# RFID_DC_Sch.net
KiCad netlist of a schematic drawn in Altium Designer
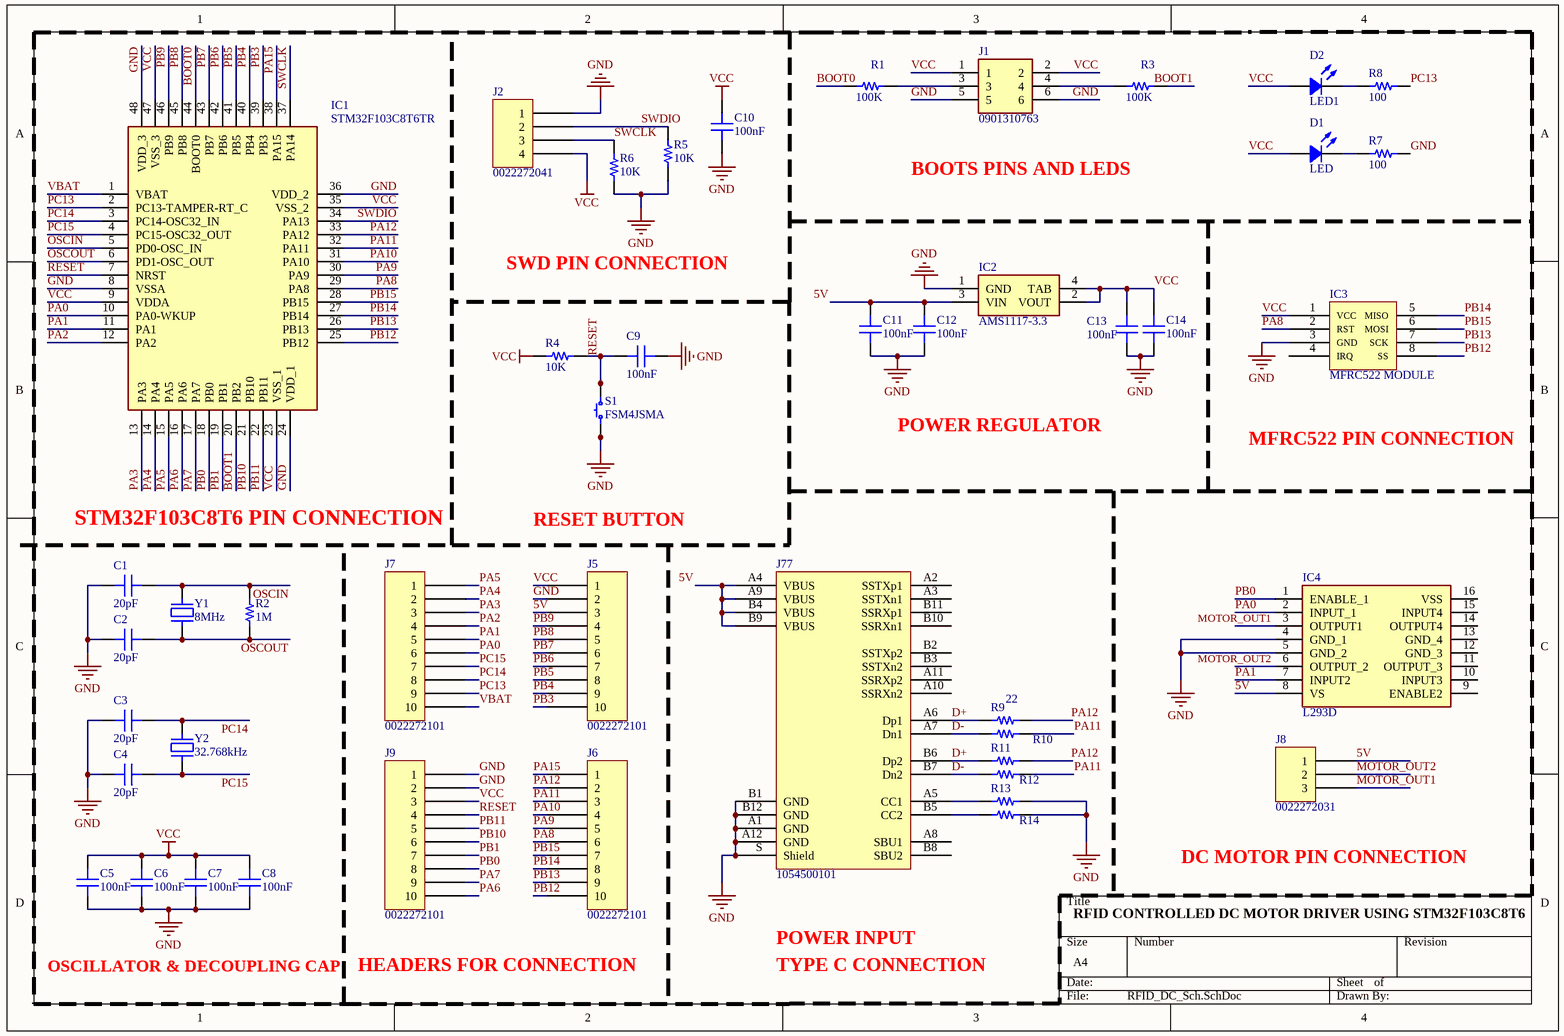
[diagram p0: RFID_DC_Sch.SchDoc]

(export (version "E")
  (design (tool "Eeschema 10.0.6"))
  (components
    (comp (ref "C1")
      (value "20pF")
      (footprint "CAP 0805_2012")
      (description "CAP CER 0.1UF 16V Y5V 0805")
      (fields (field (name "PART NUMBER") "C0805C104M4VACTU") (field (name "MANUFACTURER") "KEMET"))
      (libsource (lib "Celestial Altium Library - altium_library") (part "Capacitor"))
    )
    (comp (ref "C2")
      (value "20pF")
      (footprint "CAP 0805_2012")
      (description "CAP CER 0.1UF 16V Y5V 0805")
      (fields (field (name "PART NUMBER") "C0805C104M4VACTU") (field (name "MANUFACTURER") "KEMET"))
      (libsource (lib "Celestial Altium Library - altium_library") (part "Capacitor"))
    )
    (comp (ref "C3")
      (value "20pF")
      (footprint "CAP 0805_2012")
      (description "CAP CER 0.1UF 16V Y5V 0805")
      (fields (field (name "PART NUMBER") "C0805C104M4VACTU") (field (name "MANUFACTURER") "KEMET"))
      (libsource (lib "Celestial Altium Library - altium_library") (part "Capacitor"))
    )
    (comp (ref "C4")
      (value "20pF")
      (footprint "CAP 0805_2012")
      (description "CAP CER 0.1UF 16V Y5V 0805")
      (fields (field (name "PART NUMBER") "C0805C104M4VACTU") (field (name "MANUFACTURER") "KEMET"))
      (libsource (lib "Celestial Altium Library - altium_library") (part "Capacitor"))
    )
    (comp (ref "C5")
      (value "100nF")
      (footprint "CAP 0805_2012")
      (description "CAP CER 0.1UF 16V Y5V 0805")
      (fields (field (name "PART NUMBER") "C0805C104M4VACTU") (field (name "MANUFACTURER") "KEMET"))
      (libsource (lib "Celestial Altium Library - altium_library") (part "Capacitor"))
    )
    (comp (ref "C6")
      (value "100nF")
      (footprint "CAP 0805_2012")
      (description "CAP CER 0.1UF 16V Y5V 0805")
      (fields (field (name "PART NUMBER") "C0805C104M4VACTU") (field (name "MANUFACTURER") "KEMET"))
      (libsource (lib "Celestial Altium Library - altium_library") (part "Capacitor"))
    )
    (comp (ref "C7")
      (value "100nF")
      (footprint "CAP 0805_2012")
      (description "CAP CER 0.1UF 16V Y5V 0805")
      (fields (field (name "PART NUMBER") "C0805C104M4VACTU") (field (name "MANUFACTURER") "KEMET"))
      (libsource (lib "Celestial Altium Library - altium_library") (part "Capacitor"))
    )
    (comp (ref "C8")
      (value "100nF")
      (footprint "CAP 0805_2012")
      (description "CAP CER 0.1UF 16V Y5V 0805")
      (fields (field (name "PART NUMBER") "C0805C104M4VACTU") (field (name "MANUFACTURER") "KEMET"))
      (libsource (lib "Celestial Altium Library - altium_library") (part "Capacitor"))
    )
    (comp (ref "C9")
      (value "100nF")
      (footprint "CAP 0805_2012")
      (description "CAP CER 0.1UF 16V Y5V 0805")
      (fields (field (name "PART NUMBER") "C0805C104M4VACTU") (field (name "MANUFACTURER") "KEMET"))
      (libsource (lib "Celestial Altium Library - altium_library") (part "Capacitor"))
    )
    (comp (ref "C10")
      (value "100nF")
      (footprint "CAP 0805_2012")
      (description "CAP CER 0.1UF 16V Y5V 0805")
      (fields (field (name "PART NUMBER") "C0805C104M4VACTU") (field (name "MANUFACTURER") "KEMET"))
      (libsource (lib "Celestial Altium Library - altium_library") (part "Capacitor"))
    )
    (comp (ref "C11")
      (value "100nF")
      (footprint "CAP 0805_2012")
      (description "CAP CER 0.1UF 16V Y5V 0805")
      (fields (field (name "PART NUMBER") "C0805C104M4VACTU") (field (name "MANUFACTURER") "KEMET"))
      (libsource (lib "Celestial Altium Library - altium_library") (part "Capacitor"))
    )
    (comp (ref "C12")
      (value "100nF")
      (footprint "CAP 0805_2012")
      (description "CAP CER 0.1UF 16V Y5V 0805")
      (fields (field (name "PART NUMBER") "C0805C104M4VACTU") (field (name "MANUFACTURER") "KEMET"))
      (libsource (lib "Celestial Altium Library - altium_library") (part "Capacitor"))
    )
    (comp (ref "C13")
      (value "100nF")
      (footprint "CAP 0805_2012")
      (description "CAP CER 0.1UF 16V Y5V 0805")
      (fields (field (name "PART NUMBER") "C0805C104M4VACTU") (field (name "MANUFACTURER") "KEMET"))
      (libsource (lib "Celestial Altium Library - altium_library") (part "Capacitor"))
    )
    (comp (ref "C14")
      (value "100nF")
      (footprint "CAP 0805_2012")
      (description "CAP CER 0.1UF 16V Y5V 0805")
      (fields (field (name "PART NUMBER") "C0805C104M4VACTU") (field (name "MANUFACTURER") "KEMET"))
      (libsource (lib "Celestial Altium Library - altium_library") (part "Capacitor"))
    )
    (comp (ref "D1")
      (value "LED")
      (footprint "CREE J 2835")
      (description "LED WHITE  4000K JE2835 3V")
      (fields
        (field (name "PART NUMBER") "JE2835AWT-R-U40GA0000-N0000001")
        (field (name "MANUFACTURER") "Cree Inc.")
      )
      (libsource (lib "Celestial Altium Library - altium_library") (part "LED"))
    )
    (comp (ref "D2")
      (value "LED1")
      (footprint "CREE J 2835")
      (description "LED WHITE  4000K JE2835 3V")
      (fields
        (field (name "PART NUMBER") "JE2835AWT-R-U40GA0000-N0000001")
        (field (name "MANUFACTURER") "Cree Inc.")
      )
      (libsource (lib "Celestial Altium Library - altium_library") (part "LED"))
    )
    (comp (ref "IC1")
      (value "STM32F103C8T6TR")
      (footprint "SamacSys:QFP50P900X900X160-48N")
      (description "Integrated Circuit")
      (fields (field (name "MOUSER PART NUMBER") "511-STM32F103C8T6TR"))
      (libsource (lib "SamacSys") (part "STM32F103C8T6TR"))
    )
    (comp (ref "IC2")
      (value "AMS1117-3.3")
      (footprint "SamacSys:SOT229P700X180-4N")
      (description "Integrated Circuit")
      (libsource (lib "SamacSys") (part "AMS1117-3.3"))
    )
    (comp (ref "IC3")
      (value "MFRC522 MODULE")
      (footprint "RC522")
      (description "RFID MODULE")
      (libsource (lib "SamacSys") (part "MFRC522 MODULE"))
    )
    (comp (ref "IC4")
      (value "L293D")
      (footprint "DIP880W50P254L2000H510Q16N")
      (description "Integrated Circuit")
      (fields (field (name "MOUSER PART NUMBER") "511-L293D"))
      (libsource (lib "SamacSys") (part "L293D"))
    )
    (comp (ref "J1")
      (value "0901310763")
      (footprint "SamacSys:HDRV6W90P254_2X3_762X500X560P")
      (description "Connector")
      (libsource (lib "SamacSys") (part "0901310763"))
    )
    (comp (ref "J2")
      (value "0022272041")
      (footprint "MOLEX KK 0022272041")
      (description "CONN HEADER VERT 4POS 2.54MM")
      (fields (field (name "MANUFACTURER") "Molex"))
      (libsource (lib "Celestial Altium Library - altium_library") (part "4 Pin"))
    )
    (comp (ref "J5")
      (value "0022272101")
      (footprint "MOLEX KK 0022272101")
      (description "CONN HEADER VERT 10POS 2.54MM")
      (fields (field (name "MANUFACTURER") "Molex"))
      (libsource (lib "Celestial Altium Library - altium_library") (part "10 Pin"))
    )
    (comp (ref "J6")
      (value "0022272101")
      (footprint "MOLEX KK 0022272101")
      (description "CONN HEADER VERT 10POS 2.54MM")
      (fields (field (name "MANUFACTURER") "Molex"))
      (libsource (lib "Celestial Altium Library - altium_library") (part "10 Pin"))
    )
    (comp (ref "J7")
      (value "0022272101")
      (footprint "MOLEX KK 0022272101")
      (description "CONN HEADER VERT 10POS 2.54MM")
      (fields (field (name "MANUFACTURER") "Molex"))
      (libsource (lib "") (part "10 Pin_1"))
    )
    (comp (ref "J8")
      (value "0022272031")
      (footprint "MOLEX KK 0022272031")
      (description "CONN HEADER VERT 3POS 2.54MM")
      (fields (field (name "MANUFACTURER") "Molex"))
      (libsource (lib "Celestial Altium Library - altium_library") (part "3 Pin"))
    )
    (comp (ref "J9")
      (value "0022272101")
      (footprint "MOLEX KK 0022272101")
      (description "CONN HEADER VERT 10POS 2.54MM")
      (fields (field (name "MANUFACTURER") "Molex"))
      (libsource (lib "") (part "10 Pin_1"))
    )
    (comp (ref "J77")
      (value "1054500101")
      (footprint "Molex 1054500101")
      (description "CONN RCP USB3.1 TYPEC 24P SMD RA")
      (fields (field (name "MANUFACTURER") "Molex"))
      (libsource (lib "Celestial Altium Library - altium_library") (part "USB 3.0 Type C"))
    )
    (comp (ref "R1")
      (value "100K")
      (footprint "RES 0805_2012")
      (description "RES 931K OHM 1% 1/8W 0805")
      (fields
        (field (name "PART NUMBER") "RMCF0805FT931K")
        (field (name "MANUFACTURER") "Stackpole Electronics Inc")
      )
      (libsource (lib "Celestial Altium Library - altium_library") (part "Resistor"))
    )
    (comp (ref "R2")
      (value "1M")
      (footprint "RES 0805_2012")
      (description "RES 931K OHM 1% 1/8W 0805")
      (fields
        (field (name "PART NUMBER") "RMCF0805FT931K")
        (field (name "MANUFACTURER") "Stackpole Electronics Inc")
      )
      (libsource (lib "Celestial Altium Library - altium_library") (part "Resistor"))
    )
    (comp (ref "R3")
      (value "100K")
      (footprint "RES 0805_2012")
      (description "RES 931K OHM 1% 1/8W 0805")
      (fields
        (field (name "PART NUMBER") "RMCF0805FT931K")
        (field (name "MANUFACTURER") "Stackpole Electronics Inc")
      )
      (libsource (lib "Celestial Altium Library - altium_library") (part "Resistor"))
    )
    (comp (ref "R4")
      (value "10K")
      (footprint "RES 0805_2012")
      (description "RES 931K OHM 1% 1/8W 0805")
      (fields
        (field (name "PART NUMBER") "RMCF0805FT931K")
        (field (name "MANUFACTURER") "Stackpole Electronics Inc")
      )
      (libsource (lib "Celestial Altium Library - altium_library") (part "Resistor"))
    )
    (comp (ref "R5")
      (value "10K")
      (footprint "RES 0805_2012")
      (description "RES 931K OHM 1% 1/8W 0805")
      (fields
        (field (name "PART NUMBER") "RMCF0805FT931K")
        (field (name "MANUFACTURER") "Stackpole Electronics Inc")
      )
      (libsource (lib "Celestial Altium Library - altium_library") (part "Resistor"))
    )
    (comp (ref "R6")
      (value "10K")
      (footprint "RES 0805_2012")
      (description "RES 931K OHM 1% 1/8W 0805")
      (fields
        (field (name "PART NUMBER") "RMCF0805FT931K")
        (field (name "MANUFACTURER") "Stackpole Electronics Inc")
      )
      (libsource (lib "Celestial Altium Library - altium_library") (part "Resistor"))
    )
    (comp (ref "R7")
      (value "100")
      (footprint "RES 0805_2012")
      (description "RES 931K OHM 1% 1/8W 0805")
      (fields
        (field (name "PART NUMBER") "RMCF0805FT931K")
        (field (name "MANUFACTURER") "Stackpole Electronics Inc")
      )
      (libsource (lib "Celestial Altium Library - altium_library") (part "Resistor"))
    )
    (comp (ref "R8")
      (value "100")
      (footprint "RES 0805_2012")
      (description "RES 931K OHM 1% 1/8W 0805")
      (fields
        (field (name "PART NUMBER") "RMCF0805FT931K")
        (field (name "MANUFACTURER") "Stackpole Electronics Inc")
      )
      (libsource (lib "Celestial Altium Library - altium_library") (part "Resistor"))
    )
    (comp (ref "R9")
      (value "22")
      (footprint "RES 0805_2012")
      (description "RES 931K OHM 1% 1/8W 0805")
      (fields
        (field (name "PART NUMBER") "RMCF0805FT931K")
        (field (name "MANUFACTURER") "Stackpole Electronics Inc")
      )
      (libsource (lib "Celestial Altium Library - altium_library") (part "Resistor"))
    )
    (comp (ref "R10")
      (value "~")
      (footprint "RES 0805_2012")
      (description "RES 931K OHM 1% 1/8W 0805")
      (fields
        (field (name "PART NUMBER") "RMCF0805FT931K")
        (field (name "MANUFACTURER") "Stackpole Electronics Inc")
      )
      (libsource (lib "Celestial Altium Library - altium_library") (part "Resistor"))
    )
    (comp (ref "R11")
      (value "~")
      (footprint "RES 0805_2012")
      (description "RES 931K OHM 1% 1/8W 0805")
      (fields
        (field (name "PART NUMBER") "RMCF0805FT931K")
        (field (name "MANUFACTURER") "Stackpole Electronics Inc")
      )
      (libsource (lib "Celestial Altium Library - altium_library") (part "Resistor"))
    )
    (comp (ref "R12")
      (value "~")
      (footprint "RES 0805_2012")
      (description "RES 931K OHM 1% 1/8W 0805")
      (fields
        (field (name "PART NUMBER") "RMCF0805FT931K")
        (field (name "MANUFACTURER") "Stackpole Electronics Inc")
      )
      (libsource (lib "Celestial Altium Library - altium_library") (part "Resistor"))
    )
    (comp (ref "R13")
      (value "~")
      (footprint "RES 0805_2012")
      (description "RES 931K OHM 1% 1/8W 0805")
      (fields
        (field (name "PART NUMBER") "RMCF0805FT931K")
        (field (name "MANUFACTURER") "Stackpole Electronics Inc")
      )
      (libsource (lib "Celestial Altium Library - altium_library") (part "Resistor"))
    )
    (comp (ref "R14")
      (value "~")
      (footprint "RES 0805_2012")
      (description "RES 931K OHM 1% 1/8W 0805")
      (fields
        (field (name "PART NUMBER") "RMCF0805FT931K")
        (field (name "MANUFACTURER") "Stackpole Electronics Inc")
      )
      (libsource (lib "Celestial Altium Library - altium_library") (part "Resistor"))
    )
    (comp (ref "S1")
      (value "FSM4JSMA")
      (footprint "TE FSM4JSMA")
      (description "SWITCH TACTILE SPST-NO 0.05A 24V")
      (fields (field (name "MANUFACTURER") "TE Connectivity ALCOSWITCH Switches"))
      (libsource (lib "Celestial Altium Library - altium_library") (part "SPST-NO 4 PIN"))
    )
    (comp (ref "Y1")
      (value "8MHz")
      (footprint "ABRACON ABLS")
      (description "CRYSTAL 8.0000MHZ 18PF SMD")
      (fields (field (name "PART NUMBER") "ABLS-8.000MHZ-D-T") (field (name "MANUFACTURER") "Abracon LLC"))
      (libsource (lib "Celestial Altium Library - altium_library") (part "Abracon Crystal ABLS"))
    )
    (comp (ref "Y2")
      (value "32.768kHz")
      (footprint "ABRACON ABS07")
      (description "CRYSTAL 32.768KHZ 9PF SMD")
      (fields
        (field (name "PART NUMBER") "ABS07-32.768KHZ-9-1-T")
        (field (name "MANUFACTURER") "Abracon LLC")
      )
      (libsource (lib "Celestial Altium Library - altium_library") (part "Abracon Crystal ABS07"))
    )
  )
  (nets
    (net (code "1") (name "/5V") (class "Default")
      (node (ref "C11") (pin "2") (pinfunction "2_2") (pintype "passive"))
      (node (ref "C12") (pin "2") (pinfunction "2_2") (pintype "passive"))
      (node (ref "IC2") (pin "3") (pinfunction "VIN_3") (pintype "passive"))
      (node (ref "IC4") (pin "8") (pinfunction "VS_8") (pintype "passive"))
      (node (ref "J5") (pin "3") (pinfunction "3_3") (pintype "passive"))
      (node (ref "J77") (pin "A4") (pinfunction "VBUS_A4") (pintype "passive"))
      (node (ref "J77") (pin "A9") (pinfunction "VBUS_A9") (pintype "passive"))
      (node (ref "J77") (pin "B4") (pinfunction "VBUS_B4") (pintype "passive"))
      (node (ref "J77") (pin "B9") (pinfunction "VBUS_B9") (pintype "passive"))
      (node (ref "J8") (pin "1") (pinfunction "1_1") (pintype "passive"))
    )
    (net (code "2") (name "/BOOT0") (class "Default")
      (node (ref "IC1") (pin "44") (pinfunction "BOOT0_44") (pintype "passive"))
      (node (ref "R1") (pin "1") (pinfunction "1_1") (pintype "passive"))
    )
    (net (code "3") (name "/BOOT1") (class "Default")
      (node (ref "IC1") (pin "20") (pinfunction "PB2_20") (pintype "passive"))
      (node (ref "R3") (pin "2") (pinfunction "2_2") (pintype "passive"))
    )
    (net (code "4") (name "/D+") (class "Default")
      (node (ref "J77") (pin "A6") (pinfunction "Dp1_A6") (pintype "passive"))
      (node (ref "J77") (pin "B6") (pinfunction "Dp2_B6") (pintype "passive"))
      (node (ref "R11") (pin "2") (pinfunction "2_2") (pintype "passive"))
      (node (ref "R9") (pin "2") (pinfunction "2_2") (pintype "passive"))
    )
    (net (code "5") (name "/D-") (class "Default")
      (node (ref "J77") (pin "A7") (pinfunction "Dn1_A7") (pintype "passive"))
      (node (ref "J77") (pin "B7") (pinfunction "Dn2_B7") (pintype "passive"))
      (node (ref "R10") (pin "2") (pinfunction "2_2") (pintype "passive"))
      (node (ref "R12") (pin "2") (pinfunction "2_2") (pintype "passive"))
    )
    (net (code "6") (name "/MOTOR_OUT1") (class "Default")
      (node (ref "IC4") (pin "3") (pinfunction "OUTPUT1_3") (pintype "passive"))
      (node (ref "J8") (pin "3") (pinfunction "3_3") (pintype "passive"))
    )
    (net (code "7") (name "/MOTOR_OUT2") (class "Default")
      (node (ref "IC4") (pin "6") (pinfunction "OUTPUT_2_6") (pintype "passive"))
      (node (ref "J8") (pin "2") (pinfunction "2_2") (pintype "passive"))
    )
    (net (code "8") (name "/OSCIN") (class "Default")
      (node (ref "C1") (pin "2") (pinfunction "2_2") (pintype "passive"))
      (node (ref "IC1") (pin "5") (pinfunction "PD0-OSC_IN_5") (pintype "passive"))
      (node (ref "R2") (pin "2") (pinfunction "2_2") (pintype "passive"))
      (node (ref "Y1") (pin "2") (pinfunction "2_2") (pintype "passive"))
    )
    (net (code "9") (name "/OSCOUT") (class "Default")
      (node (ref "C2") (pin "2") (pinfunction "2_2") (pintype "passive"))
      (node (ref "IC1") (pin "6") (pinfunction "PD1-OSC_OUT_6") (pintype "passive"))
      (node (ref "R2") (pin "1") (pinfunction "1_1") (pintype "passive"))
      (node (ref "Y1") (pin "1") (pinfunction "1_1") (pintype "passive"))
    )
    (net (code "10") (name "/PA0") (class "Default")
      (node (ref "IC1") (pin "10") (pinfunction "PA0-WKUP_10") (pintype "passive"))
      (node (ref "IC4") (pin "2") (pinfunction "INPUT_1_2") (pintype "passive"))
      (node (ref "J7") (pin "6") (pinfunction "6_6") (pintype "passive"))
    )
    (net (code "11") (name "/PA1") (class "Default")
      (node (ref "IC1") (pin "11") (pinfunction "PA1_11") (pintype "passive"))
      (node (ref "IC4") (pin "7") (pinfunction "INPUT2_7") (pintype "passive"))
      (node (ref "J7") (pin "5") (pinfunction "5_5") (pintype "passive"))
    )
    (net (code "12") (name "/PA2") (class "Default")
      (node (ref "IC1") (pin "12") (pinfunction "PA2_12") (pintype "passive"))
      (node (ref "J7") (pin "4") (pinfunction "4_4") (pintype "passive"))
    )
    (net (code "13") (name "/PA3") (class "Default")
      (node (ref "IC1") (pin "13") (pinfunction "PA3_13") (pintype "passive"))
      (node (ref "J7") (pin "3") (pinfunction "3_3") (pintype "passive"))
    )
    (net (code "14") (name "/PA4") (class "Default")
      (node (ref "IC1") (pin "14") (pinfunction "PA4_14") (pintype "passive"))
      (node (ref "J7") (pin "2") (pinfunction "2_2") (pintype "passive"))
    )
    (net (code "15") (name "/PA5") (class "Default")
      (node (ref "IC1") (pin "15") (pinfunction "PA5_15") (pintype "passive"))
      (node (ref "J7") (pin "1") (pinfunction "1_1") (pintype "passive"))
    )
    (net (code "16") (name "/PA6") (class "Default")
      (node (ref "IC1") (pin "16") (pinfunction "PA6_16") (pintype "passive"))
      (node (ref "J9") (pin "10") (pinfunction "10_10") (pintype "passive"))
    )
    (net (code "17") (name "/PA7") (class "Default")
      (node (ref "IC1") (pin "17") (pinfunction "PA7_17") (pintype "passive"))
      (node (ref "J9") (pin "9") (pinfunction "9_9") (pintype "passive"))
    )
    (net (code "18") (name "/PA8") (class "Default")
      (node (ref "IC1") (pin "29") (pinfunction "PA8_29") (pintype "passive"))
      (node (ref "IC3") (pin "2") (pinfunction "RST_2") (pintype "passive"))
      (node (ref "J6") (pin "6") (pinfunction "6_6") (pintype "passive"))
    )
    (net (code "19") (name "/PA9") (class "Default")
      (node (ref "IC1") (pin "30") (pinfunction "PA9_30") (pintype "passive"))
      (node (ref "J6") (pin "5") (pinfunction "5_5") (pintype "passive"))
    )
    (net (code "20") (name "/PA10") (class "Default")
      (node (ref "IC1") (pin "31") (pinfunction "PA10_31") (pintype "passive"))
      (node (ref "J6") (pin "4") (pinfunction "4_4") (pintype "passive"))
    )
    (net (code "21") (name "/PA11") (class "Default")
      (node (ref "IC1") (pin "32") (pinfunction "PA11_32") (pintype "passive"))
      (node (ref "J6") (pin "3") (pinfunction "3_3") (pintype "passive"))
      (node (ref "R10") (pin "1") (pinfunction "1_1") (pintype "passive"))
      (node (ref "R12") (pin "1") (pinfunction "1_1") (pintype "passive"))
    )
    (net (code "22") (name "/PA12") (class "Default")
      (node (ref "IC1") (pin "33") (pinfunction "PA12_33") (pintype "passive"))
      (node (ref "J6") (pin "2") (pinfunction "2_2") (pintype "passive"))
      (node (ref "R11") (pin "1") (pinfunction "1_1") (pintype "passive"))
      (node (ref "R9") (pin "1") (pinfunction "1_1") (pintype "passive"))
    )
    (net (code "23") (name "/PA15") (class "Default")
      (node (ref "IC1") (pin "38") (pinfunction "PA15_38") (pintype "passive"))
      (node (ref "J6") (pin "1") (pinfunction "1_1") (pintype "passive"))
    )
    (net (code "24") (name "/PB0") (class "Default")
      (node (ref "IC1") (pin "18") (pinfunction "PB0_18") (pintype "passive"))
      (node (ref "IC4") (pin "1") (pinfunction "ENABLE_1_1") (pintype "passive"))
      (node (ref "J9") (pin "8") (pinfunction "8_8") (pintype "passive"))
    )
    (net (code "25") (name "/PB1") (class "Default")
      (node (ref "IC1") (pin "19") (pinfunction "PB1_19") (pintype "passive"))
      (node (ref "J9") (pin "7") (pinfunction "7_7") (pintype "passive"))
    )
    (net (code "26") (name "/PB3") (class "Default")
      (node (ref "IC1") (pin "39") (pinfunction "PB3_39") (pintype "passive"))
      (node (ref "J5") (pin "10") (pinfunction "10_10") (pintype "passive"))
    )
    (net (code "27") (name "/PB4") (class "Default")
      (node (ref "IC1") (pin "40") (pinfunction "PB4_40") (pintype "passive"))
      (node (ref "J5") (pin "9") (pinfunction "9_9") (pintype "passive"))
    )
    (net (code "28") (name "/PB5") (class "Default")
      (node (ref "IC1") (pin "41") (pinfunction "PB5_41") (pintype "passive"))
      (node (ref "J5") (pin "8") (pinfunction "8_8") (pintype "passive"))
    )
    (net (code "29") (name "/PB6") (class "Default")
      (node (ref "IC1") (pin "42") (pinfunction "PB6_42") (pintype "passive"))
      (node (ref "J5") (pin "7") (pinfunction "7_7") (pintype "passive"))
    )
    (net (code "30") (name "/PB7") (class "Default")
      (node (ref "IC1") (pin "43") (pinfunction "PB7_43") (pintype "passive"))
      (node (ref "J5") (pin "6") (pinfunction "6_6") (pintype "passive"))
    )
    (net (code "31") (name "/PB8") (class "Default")
      (node (ref "IC1") (pin "45") (pinfunction "PB8_45") (pintype "passive"))
      (node (ref "J5") (pin "5") (pinfunction "5_5") (pintype "passive"))
    )
    (net (code "32") (name "/PB9") (class "Default")
      (node (ref "IC1") (pin "46") (pinfunction "PB9_46") (pintype "passive"))
      (node (ref "J5") (pin "4") (pinfunction "4_4") (pintype "passive"))
    )
    (net (code "33") (name "/PB10") (class "Default")
      (node (ref "IC1") (pin "21") (pinfunction "PB10_21") (pintype "passive"))
      (node (ref "J9") (pin "6") (pinfunction "6_6") (pintype "passive"))
    )
    (net (code "34") (name "/PB11") (class "Default")
      (node (ref "IC1") (pin "22") (pinfunction "PB11_22") (pintype "passive"))
      (node (ref "J9") (pin "5") (pinfunction "5_5") (pintype "passive"))
    )
    (net (code "35") (name "/PB12") (class "Default")
      (node (ref "IC1") (pin "25") (pinfunction "PB12_25") (pintype "passive"))
      (node (ref "IC3") (pin "8") (pinfunction "SS_8") (pintype "passive"))
      (node (ref "J6") (pin "10") (pinfunction "10_10") (pintype "passive"))
    )
    (net (code "36") (name "/PB13") (class "Default")
      (node (ref "IC1") (pin "26") (pinfunction "PB13_26") (pintype "passive"))
      (node (ref "IC3") (pin "7") (pinfunction "SCK_7") (pintype "passive"))
      (node (ref "J6") (pin "9") (pinfunction "9_9") (pintype "passive"))
    )
    (net (code "37") (name "/PB14") (class "Default")
      (node (ref "IC1") (pin "27") (pinfunction "PB14_27") (pintype "passive"))
      (node (ref "IC3") (pin "5") (pinfunction "MISO_5") (pintype "passive"))
      (node (ref "J6") (pin "8") (pinfunction "8_8") (pintype "passive"))
    )
    (net (code "38") (name "/PB15") (class "Default")
      (node (ref "IC1") (pin "28") (pinfunction "PB15_28") (pintype "passive"))
      (node (ref "IC3") (pin "6") (pinfunction "MOSI_6") (pintype "passive"))
      (node (ref "J6") (pin "7") (pinfunction "7_7") (pintype "passive"))
    )
    (net (code "39") (name "/PC13") (class "Default")
      (node (ref "IC1") (pin "2") (pinfunction "PC13-TAMPER-RT_C_2") (pintype "passive"))
      (node (ref "J7") (pin "9") (pinfunction "9_9") (pintype "passive"))
      (node (ref "R8") (pin "2") (pinfunction "2_2") (pintype "passive"))
    )
    (net (code "40") (name "/PC14") (class "Default")
      (node (ref "C3") (pin "2") (pinfunction "2_2") (pintype "passive"))
      (node (ref "IC1") (pin "3") (pinfunction "PC14-OSC32_IN_3") (pintype "passive"))
      (node (ref "J7") (pin "8") (pinfunction "8_8") (pintype "passive"))
      (node (ref "Y2") (pin "1") (pinfunction "1_1") (pintype "passive"))
    )
    (net (code "41") (name "/PC15") (class "Default")
      (node (ref "C4") (pin "2") (pinfunction "2_2") (pintype "passive"))
      (node (ref "IC1") (pin "4") (pinfunction "PC15-OSC32_OUT_4") (pintype "passive"))
      (node (ref "J7") (pin "7") (pinfunction "7_7") (pintype "passive"))
      (node (ref "Y2") (pin "2") (pinfunction "2_2") (pintype "passive"))
    )
    (net (code "42") (name "/RESET") (class "Default")
      (node (ref "C9") (pin "2") (pinfunction "2_2") (pintype "passive"))
      (node (ref "IC1") (pin "7") (pinfunction "NRST_7") (pintype "passive"))
      (node (ref "J9") (pin "4") (pinfunction "4_4") (pintype "passive"))
      (node (ref "R4") (pin "1") (pinfunction "1_1") (pintype "passive"))
      (node (ref "S1") (pin "3") (pinfunction "3_3") (pintype "passive"))
      (node (ref "S1") (pin "4") (pinfunction "4_4") (pintype "passive"))
    )
    (net (code "43") (name "/SWCLK") (class "Default")
      (node (ref "IC1") (pin "37") (pinfunction "PA14_37") (pintype "passive"))
      (node (ref "J2") (pin "3") (pinfunction "3_3") (pintype "passive"))
      (node (ref "R6") (pin "1") (pinfunction "1_1") (pintype "passive"))
    )
    (net (code "44") (name "/SWDIO") (class "Default")
      (node (ref "IC1") (pin "34") (pinfunction "PA13_34") (pintype "passive"))
      (node (ref "J2") (pin "2") (pinfunction "2_2") (pintype "passive"))
      (node (ref "R5") (pin "2") (pinfunction "2_2") (pintype "passive"))
    )
    (net (code "45") (name "/VBAT") (class "Default")
      (node (ref "IC1") (pin "1") (pinfunction "VBAT_1") (pintype "passive"))
      (node (ref "J7") (pin "10") (pinfunction "10_10") (pintype "passive"))
    )
    (net (code "46") (name "GND") (class "Default")
      (node (ref "C1") (pin "1") (pinfunction "1_1") (pintype "passive"))
      (node (ref "C10") (pin "1") (pinfunction "1_1") (pintype "passive"))
      (node (ref "C11") (pin "1") (pinfunction "1_1") (pintype "passive"))
      (node (ref "C12") (pin "1") (pinfunction "1_1") (pintype "passive"))
      (node (ref "C13") (pin "1") (pinfunction "1_1") (pintype "passive"))
      (node (ref "C14") (pin "1") (pinfunction "1_1") (pintype "passive"))
      (node (ref "C2") (pin "1") (pinfunction "1_1") (pintype "passive"))
      (node (ref "C3") (pin "1") (pinfunction "1_1") (pintype "passive"))
      (node (ref "C4") (pin "1") (pinfunction "1_1") (pintype "passive"))
      (node (ref "C5") (pin "1") (pinfunction "1_1") (pintype "passive"))
      (node (ref "C6") (pin "1") (pinfunction "1_1") (pintype "passive"))
      (node (ref "C7") (pin "1") (pinfunction "1_1") (pintype "passive"))
      (node (ref "C8") (pin "1") (pinfunction "1_1") (pintype "passive"))
      (node (ref "C9") (pin "1") (pinfunction "1_1") (pintype "passive"))
      (node (ref "IC1") (pin "24") (pinfunction "VDD_1_24") (pintype "passive"))
      (node (ref "IC1") (pin "36") (pinfunction "VDD_2_36") (pintype "passive"))
      (node (ref "IC1") (pin "48") (pinfunction "VDD_3_48") (pintype "passive"))
      (node (ref "IC1") (pin "8") (pinfunction "VSSA_8") (pintype "passive"))
      (node (ref "IC2") (pin "1") (pinfunction "GND_1") (pintype "passive"))
      (node (ref "IC3") (pin "3") (pinfunction "GND_3") (pintype "passive"))
      (node (ref "IC4") (pin "4") (pinfunction "GND_1_4") (pintype "passive"))
      (node (ref "IC4") (pin "5") (pinfunction "GND_2_5") (pintype "passive"))
      (node (ref "J1") (pin "5") (pinfunction "5_5") (pintype "passive"))
      (node (ref "J1") (pin "6") (pinfunction "6_6") (pintype "passive"))
      (node (ref "J2") (pin "1") (pinfunction "1_1") (pintype "passive"))
      (node (ref "J5") (pin "2") (pinfunction "2_2") (pintype "passive"))
      (node (ref "J77") (pin "A1") (pinfunction "GND_A1") (pintype "passive"))
      (node (ref "J77") (pin "A12") (pinfunction "GND_A12") (pintype "passive"))
      (node (ref "J77") (pin "B1") (pinfunction "GND_B1") (pintype "passive"))
      (node (ref "J77") (pin "B12") (pinfunction "GND_B12") (pintype "passive"))
      (node (ref "J77") (pin "S") (pinfunction "Shield_S") (pintype "passive"))
      (node (ref "J9") (pin "1") (pinfunction "1_1") (pintype "passive"))
      (node (ref "J9") (pin "2") (pinfunction "2_2") (pintype "passive"))
      (node (ref "R13") (pin "1") (pinfunction "1_1") (pintype "passive"))
      (node (ref "R14") (pin "1") (pinfunction "1_1") (pintype "passive"))
      (node (ref "R5") (pin "1") (pinfunction "1_1") (pintype "passive"))
      (node (ref "R6") (pin "2") (pinfunction "2_2") (pintype "passive"))
      (node (ref "R7") (pin "2") (pinfunction "2_2") (pintype "passive"))
      (node (ref "S1") (pin "1") (pinfunction "1_1") (pintype "passive"))
      (node (ref "S1") (pin "2") (pinfunction "2_2") (pintype "passive"))
    )
    (net (code "47") (name "Net-(D1-Pad2)") (class "Default")
      (node (ref "D1") (pin "2") (pinfunction "2_2") (pintype "passive"))
      (node (ref "R7") (pin "1") (pinfunction "1_1") (pintype "passive"))
    )
    (net (code "48") (name "Net-(D2-Pad2)") (class "Default")
      (node (ref "D2") (pin "2") (pinfunction "2_2") (pintype "passive"))
      (node (ref "R8") (pin "1") (pinfunction "1_1") (pintype "passive"))
    )
    (net (code "49") (name "Net-(J1-Pad3)") (class "Default")
      (node (ref "J1") (pin "3") (pinfunction "3_3") (pintype "passive"))
      (node (ref "R1") (pin "2") (pinfunction "2_2") (pintype "passive"))
    )
    (net (code "50") (name "Net-(J1-Pad4)") (class "Default")
      (node (ref "J1") (pin "4") (pinfunction "4_4") (pintype "passive"))
      (node (ref "R3") (pin "1") (pinfunction "1_1") (pintype "passive"))
    )
    (net (code "51") (name "Net-(J77-CC1)") (class "Default")
      (node (ref "J77") (pin "A5") (pinfunction "CC1_A5") (pintype "passive"))
      (node (ref "R13") (pin "2") (pinfunction "2_2") (pintype "passive"))
    )
    (net (code "52") (name "Net-(J77-CC2)") (class "Default")
      (node (ref "J77") (pin "B5") (pinfunction "CC2_B5") (pintype "passive"))
      (node (ref "R14") (pin "2") (pinfunction "2_2") (pintype "passive"))
    )
    (net (code "53") (name "VCC") (class "Default")
      (node (ref "C10") (pin "2") (pinfunction "2_2") (pintype "passive"))
      (node (ref "C13") (pin "2") (pinfunction "2_2") (pintype "passive"))
      (node (ref "C14") (pin "2") (pinfunction "2_2") (pintype "passive"))
      (node (ref "C5") (pin "2") (pinfunction "2_2") (pintype "passive"))
      (node (ref "C6") (pin "2") (pinfunction "2_2") (pintype "passive"))
      (node (ref "C7") (pin "2") (pinfunction "2_2") (pintype "passive"))
      (node (ref "C8") (pin "2") (pinfunction "2_2") (pintype "passive"))
      (node (ref "D1") (pin "1") (pinfunction "1_1") (pintype "passive"))
      (node (ref "D2") (pin "1") (pinfunction "1_1") (pintype "passive"))
      (node (ref "IC1") (pin "23") (pinfunction "VSS_1_23") (pintype "passive"))
      (node (ref "IC1") (pin "35") (pinfunction "VSS_2_35") (pintype "passive"))
      (node (ref "IC1") (pin "47") (pinfunction "VSS_3_47") (pintype "passive"))
      (node (ref "IC1") (pin "9") (pinfunction "VDDA_9") (pintype "passive"))
      (node (ref "IC2") (pin "2") (pinfunction "VOUT_2") (pintype "passive"))
      (node (ref "IC2") (pin "4") (pinfunction "TAB_4") (pintype "passive"))
      (node (ref "IC3") (pin "1") (pinfunction "VCC_1") (pintype "passive"))
      (node (ref "J1") (pin "1") (pinfunction "1_1") (pintype "passive"))
      (node (ref "J1") (pin "2") (pinfunction "2_2") (pintype "passive"))
      (node (ref "J2") (pin "4") (pinfunction "4_4") (pintype "passive"))
      (node (ref "J5") (pin "1") (pinfunction "1_1") (pintype "passive"))
      (node (ref "J9") (pin "3") (pinfunction "3_3") (pintype "passive"))
      (node (ref "R4") (pin "2") (pinfunction "2_2") (pintype "passive"))
    )
    (net (code "54") (name "unconnected-(IC3-IRQ-Pad4)") (class "Default")
      (node (ref "IC3") (pin "4") (pinfunction "IRQ_4") (pintype "passive"))
    )
    (net (code "55") (name "unconnected-(IC4-ENABLE2-Pad9)") (class "Default")
      (node (ref "IC4") (pin "9") (pinfunction "ENABLE2_9") (pintype "passive"))
    )
    (net (code "56") (name "unconnected-(IC4-GND_3-Pad12)") (class "Default")
      (node (ref "IC4") (pin "12") (pinfunction "GND_3_12") (pintype "passive"))
    )
    (net (code "57") (name "unconnected-(IC4-GND_4-Pad13)") (class "Default")
      (node (ref "IC4") (pin "13") (pinfunction "GND_4_13") (pintype "passive"))
    )
    (net (code "58") (name "unconnected-(IC4-INPUT3-Pad10)") (class "Default")
      (node (ref "IC4") (pin "10") (pinfunction "INPUT3_10") (pintype "passive"))
    )
    (net (code "59") (name "unconnected-(IC4-INPUT4-Pad15)") (class "Default")
      (node (ref "IC4") (pin "15") (pinfunction "INPUT4_15") (pintype "passive"))
    )
    (net (code "60") (name "unconnected-(IC4-OUTPUT4-Pad14)") (class "Default")
      (node (ref "IC4") (pin "14") (pinfunction "OUTPUT4_14") (pintype "passive"))
    )
    (net (code "61") (name "unconnected-(IC4-OUTPUT_3-Pad11)") (class "Default")
      (node (ref "IC4") (pin "11") (pinfunction "OUTPUT_3_11") (pintype "passive"))
    )
    (net (code "62") (name "unconnected-(IC4-VSS-Pad16)") (class "Default")
      (node (ref "IC4") (pin "16") (pinfunction "VSS_16") (pintype "passive"))
    )
    (net (code "63") (name "unconnected-(J77-SBU1-PadA8)") (class "Default")
      (node (ref "J77") (pin "A8") (pinfunction "SBU1_A8") (pintype "passive"))
    )
    (net (code "64") (name "unconnected-(J77-SBU2-PadB8)") (class "Default")
      (node (ref "J77") (pin "B8") (pinfunction "SBU2_B8") (pintype "passive"))
    )
    (net (code "65") (name "unconnected-(J77-SSRXn1-PadB10)") (class "Default")
      (node (ref "J77") (pin "B10") (pinfunction "SSRXn1_B10") (pintype "passive"))
    )
    (net (code "66") (name "unconnected-(J77-SSRXn2-PadA10)") (class "Default")
      (node (ref "J77") (pin "A10") (pinfunction "SSRXn2_A10") (pintype "passive"))
    )
    (net (code "67") (name "unconnected-(J77-SSRXp1-PadB11)") (class "Default")
      (node (ref "J77") (pin "B11") (pinfunction "SSRXp1_B11") (pintype "passive"))
    )
    (net (code "68") (name "unconnected-(J77-SSRXp2-PadA11)") (class "Default")
      (node (ref "J77") (pin "A11") (pinfunction "SSRXp2_A11") (pintype "passive"))
    )
    (net (code "69") (name "unconnected-(J77-SSTXn1-PadA3)") (class "Default")
      (node (ref "J77") (pin "A3") (pinfunction "SSTXn1_A3") (pintype "passive"))
    )
    (net (code "70") (name "unconnected-(J77-SSTXn2-PadB3)") (class "Default")
      (node (ref "J77") (pin "B3") (pinfunction "SSTXn2_B3") (pintype "passive"))
    )
    (net (code "71") (name "unconnected-(J77-SSTXp1-PadA2)") (class "Default")
      (node (ref "J77") (pin "A2") (pinfunction "SSTXp1_A2") (pintype "passive"))
    )
    (net (code "72") (name "unconnected-(J77-SSTXp2-PadB2)") (class "Default")
      (node (ref "J77") (pin "B2") (pinfunction "SSTXp2_B2") (pintype "passive"))
    )
  )
)
